# controller.net
KiCad netlist of a schematic drawn in EAGLE
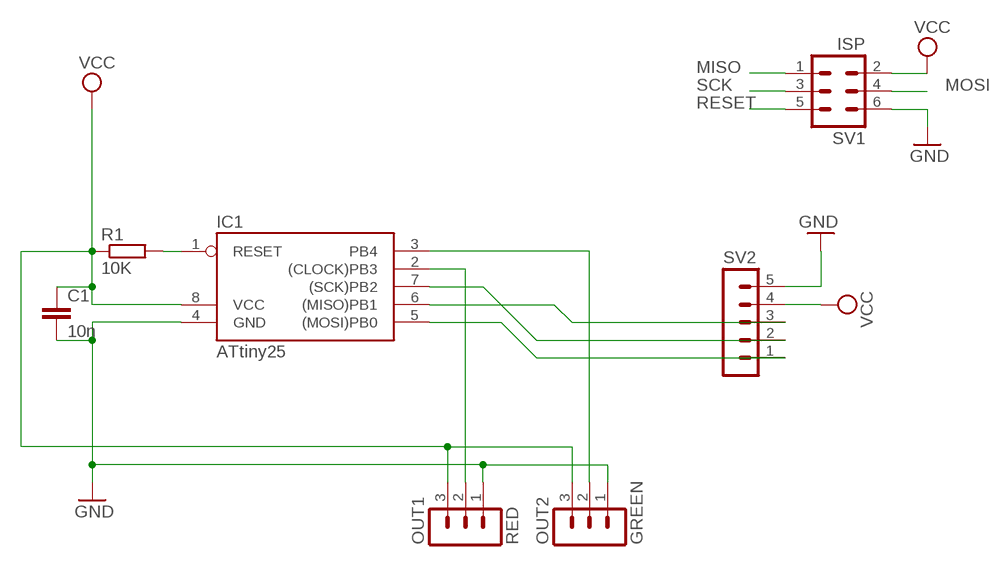
[diagram p0: schematic, sheet 1]

(export (version "E")
  (design (tool "Eeschema 10.0.6"))
  (components
    (comp (ref "C1")
      (value "10n")
      (footprint "eagle-import:C025-024X044")
      (libsource (lib "eagle-import") (part "C-EU025-024X044"))
    )
    (comp (ref "IC1")
      (value "ATtiny25")
      (footprint "eagle-import:DIL08")
      (libsource (lib "eagle-import") (part "AT902343PS"))
    )
    (comp (ref "OUT1")
      (value "RED")
      (footprint "eagle-import:MA03-1")
      (libsource (lib "eagle-import") (part "MA03-1"))
    )
    (comp (ref "OUT2")
      (value "GREEN")
      (footprint "eagle-import:MA03-1")
      (libsource (lib "eagle-import") (part "MA03-1"))
    )
    (comp (ref "R1")
      (value "10K")
      (footprint "eagle-import:0207_7")
      (libsource (lib "eagle-import") (part "R-EU_0207/7"))
    )
    (comp (ref "SV1")
      (value "ISP")
      (footprint "eagle-import:MA03-2")
      (libsource (lib "eagle-import") (part "MA03-2"))
    )
    (comp (ref "SV2")
      (value "MA05-1")
      (footprint "eagle-import:MA05-1")
      (libsource (lib "eagle-import") (part "MA05-1"))
    )
  )
  (nets
    (net (code "1") (name "/MISO") (class "Default")
      (node (ref "IC1") (pin "6") (pinfunction "(MISO)PB1_6") (pintype "bidirectional"))
      (node (ref "SV1") (pin "1") (pinfunction "1_1") (pintype "passive"))
      (node (ref "SV2") (pin "3") (pinfunction "3_3") (pintype "passive"))
    )
    (net (code "2") (name "/MOSI") (class "Default")
      (node (ref "IC1") (pin "5") (pinfunction "(MOSI)PB0_5") (pintype "bidirectional"))
      (node (ref "SV1") (pin "4") (pinfunction "4_4") (pintype "passive"))
      (node (ref "SV2") (pin "1") (pinfunction "1_1") (pintype "passive"))
    )
    (net (code "3") (name "/RESET") (class "Default")
      (node (ref "IC1") (pin "1") (pinfunction "RESET_1") (pintype "input"))
      (node (ref "R1") (pin "2") (pinfunction "2_2") (pintype "passive"))
      (node (ref "SV1") (pin "5") (pinfunction "5_5") (pintype "passive"))
    )
    (net (code "4") (name "/SCK") (class "Default")
      (node (ref "IC1") (pin "7") (pinfunction "(SCK)PB2_7") (pintype "bidirectional"))
      (node (ref "SV1") (pin "3") (pinfunction "3_3") (pintype "passive"))
      (node (ref "SV2") (pin "2") (pinfunction "2_2") (pintype "passive"))
    )
    (net (code "5") (name "GND") (class "Default")
      (node (ref "C1") (pin "2") (pinfunction "2_2") (pintype "passive"))
      (node (ref "IC1") (pin "4") (pinfunction "GND_4") (pintype "power_in"))
      (node (ref "OUT1") (pin "1") (pinfunction "1_1") (pintype "passive"))
      (node (ref "OUT2") (pin "1") (pinfunction "1_1") (pintype "passive"))
      (node (ref "SV1") (pin "6") (pinfunction "6_6") (pintype "passive"))
      (node (ref "SV2") (pin "5") (pinfunction "5_5") (pintype "passive"))
    )
    (net (code "6") (name "Net-(IC1-(CLOCK)PB3)") (class "Default")
      (node (ref "IC1") (pin "2") (pinfunction "(CLOCK)PB3_2") (pintype "bidirectional"))
      (node (ref "OUT1") (pin "2") (pinfunction "2_2") (pintype "passive"))
    )
    (net (code "7") (name "Net-(IC1-PB4)") (class "Default")
      (node (ref "IC1") (pin "3") (pinfunction "PB4_3") (pintype "bidirectional"))
      (node (ref "OUT2") (pin "2") (pinfunction "2_2") (pintype "passive"))
    )
    (net (code "8") (name "VCC") (class "Default")
      (node (ref "C1") (pin "1") (pinfunction "1_1") (pintype "passive"))
      (node (ref "IC1") (pin "8") (pinfunction "VCC_8") (pintype "power_in"))
      (node (ref "OUT1") (pin "3") (pinfunction "3_3") (pintype "passive"))
      (node (ref "OUT2") (pin "3") (pinfunction "3_3") (pintype "passive"))
      (node (ref "R1") (pin "1") (pinfunction "1_1") (pintype "passive"))
      (node (ref "SV1") (pin "2") (pinfunction "2_2") (pintype "passive"))
      (node (ref "SV2") (pin "4") (pinfunction "4_4") (pintype "passive"))
    )
  )
)
